# ue-keyer.net
KiCad netlist of a schematic drawn in EAGLE
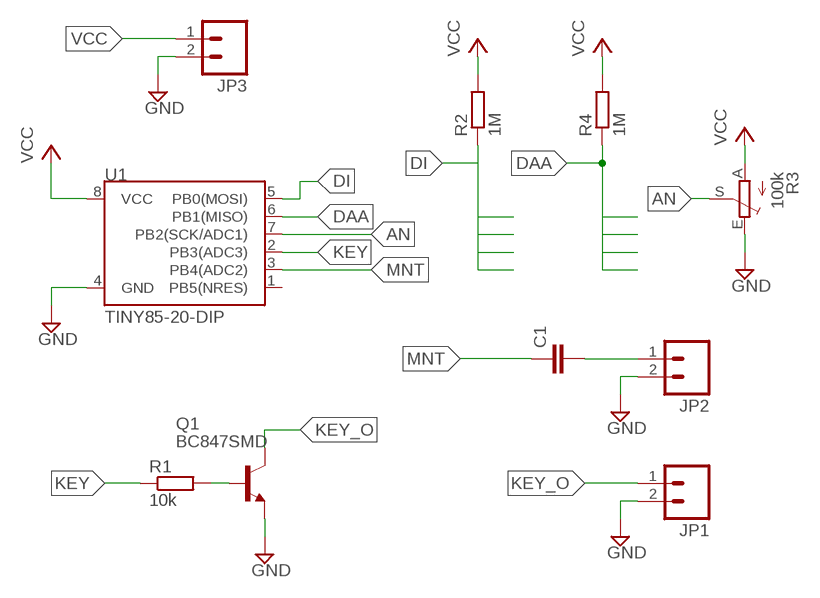
[diagram p0: schematic, sheet 1]

(export (version "E")
  (design (tool "Eeschema 10.0.6"))
  (components
    (comp (ref "C1")
      (value "C-EUC1206")
      (footprint "eagle-import:C1206")
      (libsource (lib "eagle-import") (part "C-EUC1206"))
    )
    (comp (ref "JP1")
      (value "M02LOCK_LONGPADS")
      (footprint "eagle-import:1X02_LOCK_LONGPADS")
      (libsource (lib "eagle-import") (part "M02LOCK_LONGPADS"))
    )
    (comp (ref "JP2")
      (value "M02LOCK_LONGPADS")
      (footprint "eagle-import:1X02_LOCK_LONGPADS")
      (libsource (lib "eagle-import") (part "M02LOCK_LONGPADS"))
    )
    (comp (ref "JP3")
      (value "M02LOCK_LONGPADS")
      (footprint "eagle-import:1X02_LOCK_LONGPADS")
      (libsource (lib "eagle-import") (part "M02LOCK_LONGPADS"))
    )
    (comp (ref "Q1")
      (value "BC847SMD")
      (footprint "eagle-import:SOT23")
      (libsource (lib "eagle-import") (part "BC847SMD"))
    )
    (comp (ref "R1")
      (value "10k")
      (footprint "eagle-import:R0805")
      (libsource (lib "eagle-import") (part "R-EU_R0805"))
    )
    (comp (ref "R2")
      (value "1M")
      (footprint "eagle-import:R0805")
      (libsource (lib "eagle-import") (part "R-EU_R0805"))
    )
    (comp (ref "R3")
      (value "100k")
      (footprint "eagle-import:ECP10S")
      (libsource (lib "eagle-import") (part "TRIM_EU-ECP10S"))
    )
    (comp (ref "R4")
      (value "1M")
      (footprint "eagle-import:R0805")
      (libsource (lib "eagle-import") (part "R-EU_R0805"))
    )
    (comp (ref "U1")
      (value "TINY85-20-DIP")
      (footprint "eagle-import:DIP08")
      (libsource (lib "eagle-import") (part "ATTINY45TINY85-20-DIP"))
    )
  )
  (nets
    (net (code "1") (name "AN") (class "Default")
      (node (ref "R3") (pin "S") (pinfunction "S_S") (pintype "passive"))
      (node (ref "U1") (pin "7") (pinfunction "PB2(SCK/ADC1)_7") (pintype "bidirectional"))
    )
    (net (code "2") (name "DAA") (class "Default")
      (node (ref "R4") (pin "1") (pinfunction "1_1") (pintype "passive"))
      (node (ref "U1") (pin "6") (pinfunction "PB1(MISO)_6") (pintype "bidirectional"))
    )
    (net (code "3") (name "DI") (class "Default")
      (node (ref "R2") (pin "1") (pinfunction "1_1") (pintype "passive"))
      (node (ref "U1") (pin "5") (pinfunction "PB0(MOSI)_5") (pintype "bidirectional"))
    )
    (net (code "4") (name "GND") (class "Default")
      (node (ref "JP1") (pin "2") (pinfunction "2_2") (pintype "passive"))
      (node (ref "JP2") (pin "2") (pinfunction "2_2") (pintype "passive"))
      (node (ref "JP3") (pin "2") (pinfunction "2_2") (pintype "passive"))
      (node (ref "Q1") (pin "2") (pinfunction "E_2") (pintype "passive"))
      (node (ref "R3") (pin "E") (pinfunction "E_E") (pintype "passive"))
      (node (ref "U1") (pin "4") (pinfunction "GND_4") (pintype "bidirectional"))
    )
    (net (code "5") (name "KEY") (class "Default")
      (node (ref "R1") (pin "1") (pinfunction "1_1") (pintype "passive"))
      (node (ref "U1") (pin "2") (pinfunction "PB3(ADC3)_2") (pintype "bidirectional"))
    )
    (net (code "6") (name "KEY_O") (class "Default")
      (node (ref "JP1") (pin "1") (pinfunction "1_1") (pintype "passive"))
      (node (ref "Q1") (pin "3") (pinfunction "C_3") (pintype "passive"))
    )
    (net (code "7") (name "MNT") (class "Default")
      (node (ref "C1") (pin "1") (pinfunction "1_1") (pintype "passive"))
      (node (ref "U1") (pin "3") (pinfunction "PB4(ADC2)_3") (pintype "bidirectional"))
    )
    (net (code "8") (name "Net-(C1-Pad2)") (class "Default")
      (node (ref "C1") (pin "2") (pinfunction "2_2") (pintype "passive"))
      (node (ref "JP2") (pin "1") (pinfunction "1_1") (pintype "passive"))
    )
    (net (code "9") (name "Net-(Q1-B)") (class "Default")
      (node (ref "Q1") (pin "1") (pinfunction "B_1") (pintype "passive"))
      (node (ref "R1") (pin "2") (pinfunction "2_2") (pintype "passive"))
    )
    (net (code "10") (name "VCC") (class "Default")
      (node (ref "JP3") (pin "1") (pinfunction "1_1") (pintype "passive"))
      (node (ref "R2") (pin "2") (pinfunction "2_2") (pintype "passive"))
      (node (ref "R3") (pin "A") (pinfunction "A_A") (pintype "passive"))
      (node (ref "R4") (pin "2") (pinfunction "2_2") (pintype "passive"))
      (node (ref "U1") (pin "8") (pinfunction "VCC_8") (pintype "bidirectional"))
    )
    (net (code "11") (name "unconnected-(U1-PB5(NRES)-Pad1)") (class "Default")
      (node (ref "U1") (pin "1") (pinfunction "PB5(NRES)_1") (pintype "bidirectional"))
    )
  )
)
